# tf-CARD.net
KiCad netlist of a schematic drawn in Altium Designer
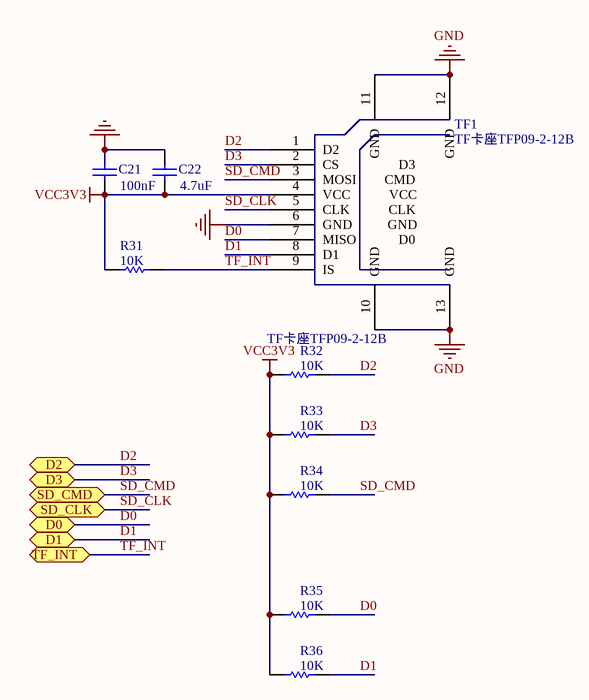
[diagram p0: tf-CARD.SchDoc]

(export (version "E")
  (design (tool "Eeschema 10.0.6"))
  (components
    (comp (ref "C21")
      (value "100nF")
      (footprint "0402")
      (description "Capacitor")
      (fields (field (name "PUBLISHER") "Altium Limited"))
      (libsource (lib "Miscellaneous Devices") (part "Cap"))
    )
    (comp (ref "C22")
      (value "4.7uF")
      (footprint "C0603N")
      (description "Capacitor")
      (fields (field (name "PUBLISHER") "Altium Limited"))
      (libsource (lib "Miscellaneous Devices") (part "Cap"))
    )
    (comp (ref "R31")
      (value "10K")
      (footprint "0402")
      (description "Semiconductor Resistor")
      (fields (field (name "PUBLISHER") "Altium Limited"))
      (libsource (lib "Miscellaneous Devices") (part "Res Semi"))
    )
    (comp (ref "R32")
      (value "10K")
      (footprint "0402")
      (description "Semiconductor Resistor")
      (fields (field (name "PUBLISHER") "Altium Limited"))
      (libsource (lib "Miscellaneous Devices") (part "Res Semi"))
    )
    (comp (ref "R33")
      (value "10K")
      (footprint "0402")
      (description "Semiconductor Resistor")
      (fields (field (name "PUBLISHER") "Altium Limited"))
      (libsource (lib "Miscellaneous Devices") (part "Res Semi"))
    )
    (comp (ref "R34")
      (value "10K")
      (footprint "0402")
      (description "Semiconductor Resistor")
      (fields (field (name "PUBLISHER") "Altium Limited"))
      (libsource (lib "Miscellaneous Devices") (part "Res Semi"))
    )
    (comp (ref "R35")
      (value "10K")
      (footprint "0402")
      (description "Semiconductor Resistor")
      (fields (field (name "PUBLISHER") "Altium Limited"))
      (libsource (lib "Miscellaneous Devices") (part "Res Semi"))
    )
    (comp (ref "R36")
      (value "10K")
      (footprint "0402")
      (description "Semiconductor Resistor")
      (fields (field (name "PUBLISHER") "Altium Limited"))
      (libsource (lib "Miscellaneous Devices") (part "Res Semi"))
    )
    (comp (ref "TF1")
      (value "TF卡座TFP09-2-12B")
      (footprint "TFP09-2-12B")
      (fields (field (name "ALTIUM_VALUE") "TF卡座TFP09-2-12B"))
      (libsource (lib "Device") (part "TF_CARD"))
    )
  )
  (nets
    (net (code "1") (name "/D0") (class "Default")
      (node (ref "R35") (pin "2") (pinfunction "2_2") (pintype "passive"))
      (node (ref "TF1") (pin "7") (pinfunction "MISO____________D0_7") (pintype "passive"))
    )
    (net (code "2") (name "/D1") (class "Default")
      (node (ref "R36") (pin "2") (pinfunction "2_2") (pintype "passive"))
      (node (ref "TF1") (pin "8") (pinfunction "D1_8") (pintype "passive"))
    )
    (net (code "3") (name "/D2") (class "Default")
      (node (ref "R32") (pin "2") (pinfunction "2_2") (pintype "passive"))
      (node (ref "TF1") (pin "1") (pinfunction "D2_1") (pintype "passive"))
    )
    (net (code "4") (name "/D3") (class "Default")
      (node (ref "R33") (pin "2") (pinfunction "2_2") (pintype "passive"))
      (node (ref "TF1") (pin "2") (pinfunction "CS_________________D3_2") (pintype "passive"))
    )
    (net (code "5") (name "/SD_CLK") (class "Default")
      (node (ref "TF1") (pin "5") (pinfunction "CLK___________CLK_5") (pintype "passive"))
    )
    (net (code "6") (name "/SD_CMD") (class "Default")
      (node (ref "R34") (pin "2") (pinfunction "2_2") (pintype "passive"))
      (node (ref "TF1") (pin "3") (pinfunction "MOSI________CMD_3") (pintype "passive"))
    )
    (net (code "7") (name "/TF_INT") (class "Default")
      (node (ref "R31") (pin "2") (pinfunction "2_2") (pintype "passive"))
      (node (ref "TF1") (pin "9") (pinfunction "IS_9") (pintype "passive"))
    )
    (net (code "8") (name "GND") (class "Default")
      (node (ref "C21") (pin "2") (pinfunction "2_2") (pintype "passive"))
      (node (ref "C22") (pin "2") (pinfunction "2_2") (pintype "passive"))
      (node (ref "TF1") (pin "10") (pinfunction "GND_10") (pintype "passive"))
      (node (ref "TF1") (pin "11") (pinfunction "GND_11") (pintype "passive"))
      (node (ref "TF1") (pin "12") (pinfunction "GND_12") (pintype "passive"))
      (node (ref "TF1") (pin "13") (pinfunction "GND_13") (pintype "passive"))
      (node (ref "TF1") (pin "6") (pinfunction "GND__________GND_6") (pintype "passive"))
    )
    (net (code "9") (name "VCC3V3") (class "Default")
      (node (ref "C21") (pin "1") (pinfunction "1_1") (pintype "passive"))
      (node (ref "C22") (pin "1") (pinfunction "1_1") (pintype "passive"))
      (node (ref "R31") (pin "1") (pinfunction "1_1") (pintype "passive"))
      (node (ref "R32") (pin "1") (pinfunction "1_1") (pintype "passive"))
      (node (ref "R33") (pin "1") (pinfunction "1_1") (pintype "passive"))
      (node (ref "R34") (pin "1") (pinfunction "1_1") (pintype "passive"))
      (node (ref "R35") (pin "1") (pinfunction "1_1") (pintype "passive"))
      (node (ref "R36") (pin "1") (pinfunction "1_1") (pintype "passive"))
      (node (ref "TF1") (pin "4") (pinfunction "VCC___________VCC_4") (pintype "passive"))
    )
  )
)
